# MPU9250_SPI.net
KiCad netlist of a schematic drawn in EAGLE
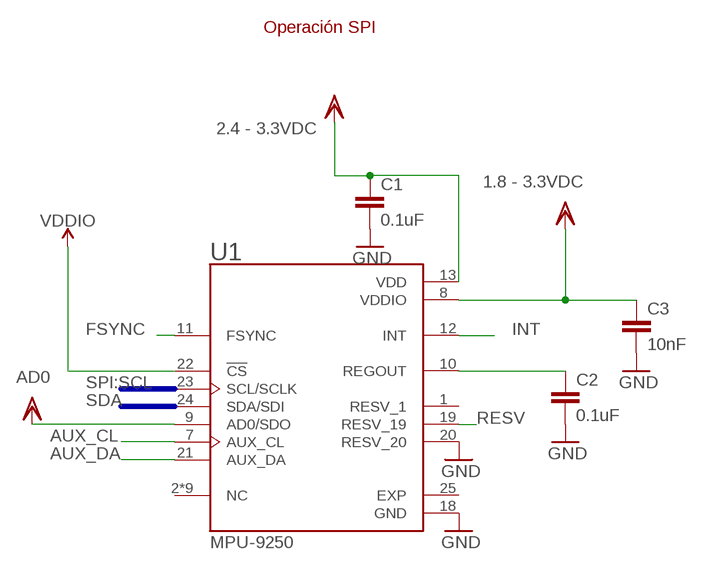
[diagram p0: schematic, sheet 1]

(export (version "E")
  (design (tool "Eeschema 10.0.6"))
  (components
    (comp (ref "C1")
      (value "0.1uF")
      (footprint "eagle-import:1206")
      (libsource (lib "eagle-import") (part "1.0NF/1000PF-1206-2KV-10%"))
    )
    (comp (ref "C2")
      (value "0.1uF")
      (footprint "eagle-import:1206")
      (libsource (lib "eagle-import") (part "1.0NF/1000PF-1206-2KV-10%"))
    )
    (comp (ref "C3")
      (value "10nF")
      (footprint "eagle-import:1206")
      (libsource (lib "eagle-import") (part "1.0NF/1000PF-1206-2KV-10%"))
    )
    (comp (ref "U1")
      (value "MPU-9250")
      (footprint "eagle-import:QFN40P300X300X105-25N")
      (fields (field (name "MF") "TDK InvenSense"))
      (libsource (lib "eagle-import") (part "MPU-9250"))
    )
  )
  (nets
    (net (code "3") (name "/AUX_CL") (class "Default")
      (node (ref "U1") (pin "7") (pinfunction "AUX_CL_7") (pintype "input"))
    )
    (net (code "4") (name "/AUX_DA") (class "Default")
      (node (ref "U1") (pin "21") (pinfunction "AUX_DA_21") (pintype "input"))
    )
    (net (code "5") (name "/FSYNC") (class "Default")
      (node (ref "U1") (pin "11") (pinfunction "FSYNC_11") (pintype "input"))
    )
    (net (code "6") (name "/INT") (class "Default")
      (node (ref "U1") (pin "12") (pinfunction "INT_12") (pintype "output"))
    )
    (net (code "8") (name "/RESV") (class "Default")
      (node (ref "U1") (pin "19") (pinfunction "RESV_19_19") (pintype "no_connect"))
    )
    (net (code "9") (name "/RESV_1") (class "Default")
      (node (ref "U1") (pin "1") (pinfunction "RESV_1_1") (pintype "power_in"))
    )
    (net (code "10") (name "/{SDA}") (class "Default")
      (node (ref "U1") (pin "24") (pinfunction "SDA/SDI_24") (pintype "bidirectional"))
    )
    (net (code "11") (name "/{SPI:SCL}") (class "Default")
      (node (ref "U1") (pin "23") (pinfunction "SCL/SCLK_23") (pintype "input"))
    )
    (net (code "12") (name "1.8 - 3.3VDC") (class "Default")
      (node (ref "C1") (pin "1") (pinfunction "1_1") (pintype "passive"))
      (node (ref "C3") (pin "1") (pinfunction "1_1") (pintype "passive"))
      (node (ref "U1") (pin "13") (pinfunction "VDD_13") (pintype "power_in"))
      (node (ref "U1") (pin "8") (pinfunction "VDDIO_8") (pintype "power_in"))
      (node (ref "U1") (pin "9") (pinfunction "AD0/SDO_9") (pintype "output"))
    )
    (net (code "13") (name "GND") (class "Default")
      (node (ref "C1") (pin "2") (pinfunction "2_2") (pintype "passive"))
      (node (ref "C2") (pin "2") (pinfunction "2_2") (pintype "passive"))
      (node (ref "C3") (pin "2") (pinfunction "2_2") (pintype "passive"))
      (node (ref "U1") (pin "18") (pinfunction "GND_18") (pintype "power_in"))
      (node (ref "U1") (pin "20") (pinfunction "RESV_20_20") (pintype "power_in"))
    )
    (net (code "14") (name "Net-(U1-REGOUT)") (class "Default")
      (node (ref "C2") (pin "1") (pinfunction "1_1") (pintype "passive"))
      (node (ref "U1") (pin "10") (pinfunction "REGOUT_10") (pintype "output"))
    )
    (net (code "15") (name "VDDIO") (class "Default")
      (node (ref "U1") (pin "22") (pinfunction "~{CS}_22") (pintype "input"))
    )
    (net (code "16") (name "unconnected-(U1-EXP-Pad25)") (class "Default")
      (node (ref "U1") (pin "25") (pinfunction "EXP_25") (pintype "passive"))
    )
    (net (code "17") (name "unconnected-(U1-NC-Pad2)") (class "Default")
      (node (ref "U1") (pin "2") (pinfunction "NC_2") (pintype "no_connect"))
    )
    (net (code "18") (name "unconnected-(U1-NC-Pad3)") (class "Default")
      (node (ref "U1") (pin "3") (pinfunction "NC_3") (pintype "no_connect"))
    )
    (net (code "19") (name "unconnected-(U1-NC-Pad4)") (class "Default")
      (node (ref "U1") (pin "4") (pinfunction "NC_4") (pintype "no_connect"))
    )
    (net (code "20") (name "unconnected-(U1-NC-Pad5)") (class "Default")
      (node (ref "U1") (pin "5") (pinfunction "NC_5") (pintype "no_connect"))
    )
    (net (code "21") (name "unconnected-(U1-NC-Pad6)") (class "Default")
      (node (ref "U1") (pin "6") (pinfunction "NC_6") (pintype "no_connect"))
    )
    (net (code "22") (name "unconnected-(U1-NC-Pad14)") (class "Default")
      (node (ref "U1") (pin "14") (pinfunction "NC_14") (pintype "no_connect"))
    )
    (net (code "23") (name "unconnected-(U1-NC-Pad15)") (class "Default")
      (node (ref "U1") (pin "15") (pinfunction "NC_15") (pintype "no_connect"))
    )
    (net (code "24") (name "unconnected-(U1-NC-Pad16)") (class "Default")
      (node (ref "U1") (pin "16") (pinfunction "NC_16") (pintype "no_connect"))
    )
    (net (code "25") (name "unconnected-(U1-NC-Pad17)") (class "Default")
      (node (ref "U1") (pin "17") (pinfunction "NC_17") (pintype "no_connect"))
    )
  )
)
